# GPS_Breakout.net
KiCad netlist of a schematic drawn in EAGLE
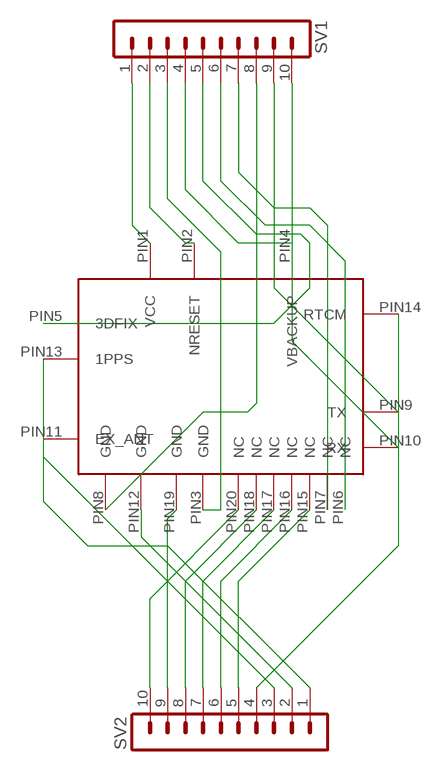
[diagram p0: schematic, sheet 1]

(export (version "E")
  (design (tool "Eeschema 10.0.6"))
  (components
    (comp (ref "SV1")
      (value "MA10-1")
      (footprint "eagle-import:MA10-1")
      (libsource (lib "eagle-import") (part "MA10-1"))
    )
    (comp (ref "SV2")
      (value "MA10-1")
      (footprint "eagle-import:MA10-1")
      (libsource (lib "eagle-import") (part "MA10-1"))
    )
    (comp (ref "U$1")
      (value "GPS_FGPMMOPA6H")
      (footprint "eagle-import:FGPMMOPA6H_FOOTPRINT")
      (libsource (lib "eagle-import") (part "GPS_FGPMMOPA6H"))
    )
  )
  (nets
    (net (code "1") (name "Net-(SV1-Pad3)") (class "Default")
      (node (ref "SV1") (pin "3") (pinfunction "3_3") (pintype "passive"))
      (node (ref "U$1") (pin "PIN3") (pinfunction "GND_PIN3") (pintype "bidirectional"))
    )
    (net (code "2") (name "Net-(SV1-Pad6)") (class "Default")
      (node (ref "SV1") (pin "6") (pinfunction "6_6") (pintype "passive"))
      (node (ref "U$1") (pin "PIN6") (pinfunction "NC_PIN6") (pintype "bidirectional"))
    )
    (net (code "3") (name "Net-(SV1-Pad7)") (class "Default")
      (node (ref "SV1") (pin "7") (pinfunction "7_7") (pintype "passive"))
      (node (ref "U$1") (pin "PIN7") (pinfunction "NC_PIN7") (pintype "bidirectional"))
    )
    (net (code "4") (name "Net-(SV1-Pad8)") (class "Default")
      (node (ref "SV1") (pin "8") (pinfunction "8_8") (pintype "passive"))
      (node (ref "U$1") (pin "PIN8") (pinfunction "GND_PIN8") (pintype "bidirectional"))
    )
    (net (code "5") (name "Net-(SV2-Pad2)") (class "Default")
      (node (ref "SV2") (pin "2") (pinfunction "2_2") (pintype "passive"))
      (node (ref "U$1") (pin "PIN12") (pinfunction "GND_PIN12") (pintype "bidirectional"))
    )
    (net (code "6") (name "Net-(SV2-Pad5)") (class "Default")
      (node (ref "SV2") (pin "5") (pinfunction "5_5") (pintype "passive"))
      (node (ref "U$1") (pin "PIN15") (pinfunction "NC_PIN15") (pintype "bidirectional"))
    )
    (net (code "7") (name "Net-(SV2-Pad6)") (class "Default")
      (node (ref "SV2") (pin "6") (pinfunction "6_6") (pintype "passive"))
      (node (ref "U$1") (pin "PIN16") (pinfunction "NC_PIN16") (pintype "bidirectional"))
    )
    (net (code "8") (name "Net-(SV2-Pad7)") (class "Default")
      (node (ref "SV2") (pin "7") (pinfunction "7_7") (pintype "passive"))
      (node (ref "U$1") (pin "PIN17") (pinfunction "NC_PIN17") (pintype "bidirectional"))
    )
    (net (code "9") (name "Net-(SV2-Pad8)") (class "Default")
      (node (ref "SV2") (pin "8") (pinfunction "8_8") (pintype "passive"))
      (node (ref "U$1") (pin "PIN18") (pinfunction "NC_PIN18") (pintype "bidirectional"))
    )
    (net (code "10") (name "Net-(SV2-Pad9)") (class "Default")
      (node (ref "SV2") (pin "9") (pinfunction "9_9") (pintype "passive"))
      (node (ref "U$1") (pin "PIN19") (pinfunction "GND_PIN19") (pintype "bidirectional"))
    )
    (net (code "11") (name "Net-(SV2-Pad10)") (class "Default")
      (node (ref "SV2") (pin "10") (pinfunction "10_10") (pintype "passive"))
      (node (ref "U$1") (pin "PIN20") (pinfunction "NC_PIN20") (pintype "bidirectional"))
    )
    (net (code "12") (name "Net-(U$1-1PPS)") (class "Default")
      (node (ref "SV2") (pin "3") (pinfunction "3_3") (pintype "passive"))
      (node (ref "U$1") (pin "PIN13") (pinfunction "1PPS_PIN13") (pintype "bidirectional"))
    )
    (net (code "13") (name "Net-(U$1-3DFIX)") (class "Default")
      (node (ref "SV1") (pin "5") (pinfunction "5_5") (pintype "passive"))
      (node (ref "U$1") (pin "PIN5") (pinfunction "3DFIX_PIN5") (pintype "bidirectional"))
    )
    (net (code "14") (name "Net-(U$1-EX_ANT)") (class "Default")
      (node (ref "SV2") (pin "1") (pinfunction "1_1") (pintype "passive"))
      (node (ref "U$1") (pin "PIN11") (pinfunction "EX_ANT_PIN11") (pintype "bidirectional"))
    )
    (net (code "15") (name "Net-(U$1-NRESET)") (class "Default")
      (node (ref "SV1") (pin "2") (pinfunction "2_2") (pintype "passive"))
      (node (ref "U$1") (pin "PIN2") (pinfunction "NRESET_PIN2") (pintype "bidirectional"))
    )
    (net (code "16") (name "Net-(U$1-RTCM)") (class "Default")
      (node (ref "SV2") (pin "4") (pinfunction "4_4") (pintype "passive"))
      (node (ref "U$1") (pin "PIN14") (pinfunction "RTCM_PIN14") (pintype "bidirectional"))
    )
    (net (code "17") (name "Net-(U$1-RX)") (class "Default")
      (node (ref "SV1") (pin "10") (pinfunction "10_10") (pintype "passive"))
      (node (ref "U$1") (pin "PIN10") (pinfunction "RX_PIN10") (pintype "bidirectional"))
    )
    (net (code "18") (name "Net-(U$1-TX)") (class "Default")
      (node (ref "SV1") (pin "9") (pinfunction "9_9") (pintype "passive"))
      (node (ref "U$1") (pin "PIN9") (pinfunction "TX_PIN9") (pintype "bidirectional"))
    )
    (net (code "19") (name "Net-(U$1-VBACKUP)") (class "Default")
      (node (ref "SV1") (pin "4") (pinfunction "4_4") (pintype "passive"))
      (node (ref "U$1") (pin "PIN4") (pinfunction "VBACKUP_PIN4") (pintype "bidirectional"))
    )
    (net (code "20") (name "Net-(U$1-VCC)") (class "Default")
      (node (ref "SV1") (pin "1") (pinfunction "1_1") (pintype "passive"))
      (node (ref "U$1") (pin "PIN1") (pinfunction "VCC_PIN1") (pintype "bidirectional"))
    )
  )
)
